# shift_reg.net
KiCad netlist of a schematic drawn in EAGLE
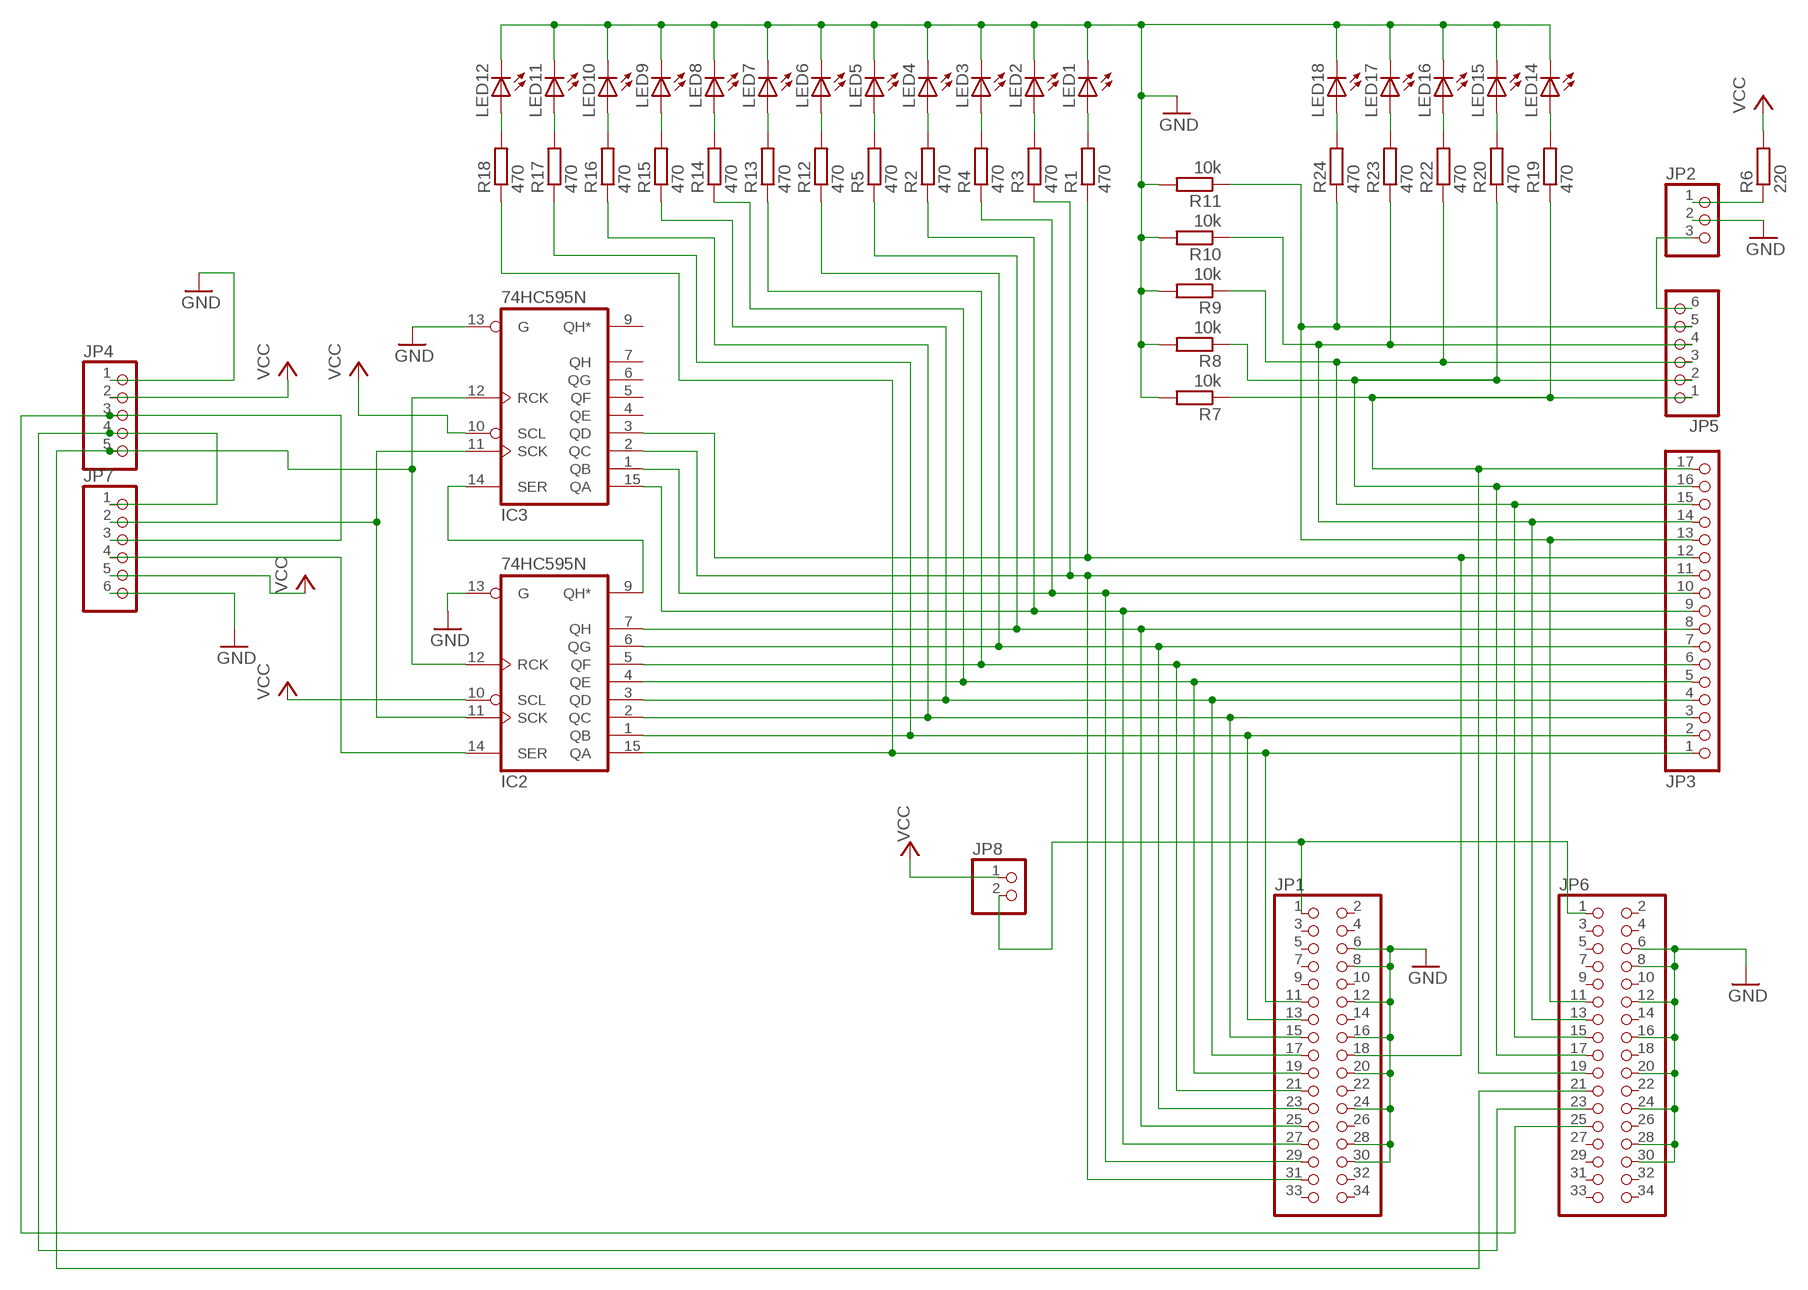
[diagram p0: schematic, sheet 1]

(export (version "E")
  (design (tool "Eeschema 10.0.6"))
  (components
    (comp (ref "IC2")
      (value "74HC595N")
      (footprint "eagle-import:DIL16")
      (libsource (lib "eagle-import") (part "74595NHC"))
    )
    (comp (ref "IC3")
      (value "74HC595N")
      (footprint "eagle-import:DIL16")
      (libsource (lib "eagle-import") (part "74595NHC"))
    )
    (comp (ref "JP1")
      (value "PINHD-2X17")
      (footprint "eagle-import:2X17")
      (libsource (lib "eagle-import") (part "PINHD-2X17"))
    )
    (comp (ref "JP2")
      (value "PINHD-1X3")
      (footprint "eagle-import:1X03")
      (libsource (lib "eagle-import") (part "PINHD-1X3"))
    )
    (comp (ref "JP3")
      (value "PINHD-1X17")
      (footprint "eagle-import:1X17")
      (libsource (lib "eagle-import") (part "PINHD-1X17"))
    )
    (comp (ref "JP4")
      (value "PINHD-1X5")
      (footprint "eagle-import:1X05")
      (libsource (lib "eagle-import") (part "PINHD-1X5"))
    )
    (comp (ref "JP5")
      (value "PINHD-1X6")
      (footprint "eagle-import:1X06")
      (libsource (lib "eagle-import") (part "PINHD-1X6"))
    )
    (comp (ref "JP6")
      (value "PINHD-2X17")
      (footprint "eagle-import:2X17")
      (libsource (lib "eagle-import") (part "PINHD-2X17"))
    )
    (comp (ref "JP7")
      (value "PINHD-1X6")
      (footprint "eagle-import:1X06")
      (libsource (lib "eagle-import") (part "PINHD-1X6"))
    )
    (comp (ref "JP8")
      (value "PINHD-1X2")
      (footprint "eagle-import:1X02")
      (libsource (lib "eagle-import") (part "PINHD-1X2"))
    )
    (comp (ref "LED1")
      (value "LED3MM")
      (footprint "eagle-import:LED3MM")
      (libsource (lib "eagle-import") (part "LED3MM"))
    )
    (comp (ref "LED2")
      (value "LED3MM")
      (footprint "eagle-import:LED3MM")
      (libsource (lib "eagle-import") (part "LED3MM"))
    )
    (comp (ref "LED3")
      (value "LED3MM")
      (footprint "eagle-import:LED3MM")
      (libsource (lib "eagle-import") (part "LED3MM"))
    )
    (comp (ref "LED4")
      (value "LED3MM")
      (footprint "eagle-import:LED3MM")
      (libsource (lib "eagle-import") (part "LED3MM"))
    )
    (comp (ref "LED5")
      (value "LED3MM")
      (footprint "eagle-import:LED3MM")
      (libsource (lib "eagle-import") (part "LED3MM"))
    )
    (comp (ref "LED6")
      (value "LED3MM")
      (footprint "eagle-import:LED3MM")
      (libsource (lib "eagle-import") (part "LED3MM"))
    )
    (comp (ref "LED7")
      (value "LED3MM")
      (footprint "eagle-import:LED3MM")
      (libsource (lib "eagle-import") (part "LED3MM"))
    )
    (comp (ref "LED8")
      (value "LED3MM")
      (footprint "eagle-import:LED3MM")
      (libsource (lib "eagle-import") (part "LED3MM"))
    )
    (comp (ref "LED9")
      (value "LED3MM")
      (footprint "eagle-import:LED3MM")
      (libsource (lib "eagle-import") (part "LED3MM"))
    )
    (comp (ref "LED10")
      (value "LED3MM")
      (footprint "eagle-import:LED3MM")
      (libsource (lib "eagle-import") (part "LED3MM"))
    )
    (comp (ref "LED11")
      (value "LED3MM")
      (footprint "eagle-import:LED3MM")
      (libsource (lib "eagle-import") (part "LED3MM"))
    )
    (comp (ref "LED12")
      (value "LED3MM")
      (footprint "eagle-import:LED3MM")
      (libsource (lib "eagle-import") (part "LED3MM"))
    )
    (comp (ref "LED14")
      (value "LED3MM")
      (footprint "eagle-import:LED3MM")
      (libsource (lib "eagle-import") (part "LED3MM"))
    )
    (comp (ref "LED15")
      (value "LED3MM")
      (footprint "eagle-import:LED3MM")
      (libsource (lib "eagle-import") (part "LED3MM"))
    )
    (comp (ref "LED16")
      (value "LED3MM")
      (footprint "eagle-import:LED3MM")
      (libsource (lib "eagle-import") (part "LED3MM"))
    )
    (comp (ref "LED17")
      (value "LED3MM")
      (footprint "eagle-import:LED3MM")
      (libsource (lib "eagle-import") (part "LED3MM"))
    )
    (comp (ref "LED18")
      (value "LED3MM")
      (footprint "eagle-import:LED3MM")
      (libsource (lib "eagle-import") (part "LED3MM"))
    )
    (comp (ref "R1")
      (value "470")
      (footprint "eagle-import:0207_10")
      (libsource (lib "eagle-import") (part "R-EU_0207/10"))
    )
    (comp (ref "R2")
      (value "470")
      (footprint "eagle-import:0207_10")
      (libsource (lib "eagle-import") (part "R-EU_0207/10"))
    )
    (comp (ref "R3")
      (value "470")
      (footprint "eagle-import:0207_10")
      (libsource (lib "eagle-import") (part "R-EU_0207/10"))
    )
    (comp (ref "R4")
      (value "470")
      (footprint "eagle-import:0207_10")
      (libsource (lib "eagle-import") (part "R-EU_0207/10"))
    )
    (comp (ref "R5")
      (value "470")
      (footprint "eagle-import:0207_10")
      (libsource (lib "eagle-import") (part "R-EU_0207/10"))
    )
    (comp (ref "R6")
      (value "220")
      (footprint "eagle-import:0207_10")
      (libsource (lib "eagle-import") (part "R-EU_0207/10"))
    )
    (comp (ref "R7")
      (value "10k")
      (footprint "eagle-import:0207_10")
      (libsource (lib "eagle-import") (part "R-EU_0207/10"))
    )
    (comp (ref "R8")
      (value "10k")
      (footprint "eagle-import:0207_10")
      (libsource (lib "eagle-import") (part "R-EU_0207/10"))
    )
    (comp (ref "R9")
      (value "10k")
      (footprint "eagle-import:0207_10")
      (libsource (lib "eagle-import") (part "R-EU_0207/10"))
    )
    (comp (ref "R10")
      (value "10k")
      (footprint "eagle-import:0207_10")
      (libsource (lib "eagle-import") (part "R-EU_0207/10"))
    )
    (comp (ref "R11")
      (value "10k")
      (footprint "eagle-import:0207_10")
      (libsource (lib "eagle-import") (part "R-EU_0207/10"))
    )
    (comp (ref "R12")
      (value "470")
      (footprint "eagle-import:0207_10")
      (libsource (lib "eagle-import") (part "R-EU_0207/10"))
    )
    (comp (ref "R13")
      (value "470")
      (footprint "eagle-import:0207_10")
      (libsource (lib "eagle-import") (part "R-EU_0207/10"))
    )
    (comp (ref "R14")
      (value "470")
      (footprint "eagle-import:0207_10")
      (libsource (lib "eagle-import") (part "R-EU_0207/10"))
    )
    (comp (ref "R15")
      (value "470")
      (footprint "eagle-import:0207_10")
      (libsource (lib "eagle-import") (part "R-EU_0207/10"))
    )
    (comp (ref "R16")
      (value "470")
      (footprint "eagle-import:0207_10")
      (libsource (lib "eagle-import") (part "R-EU_0207/10"))
    )
    (comp (ref "R17")
      (value "470")
      (footprint "eagle-import:0207_10")
      (libsource (lib "eagle-import") (part "R-EU_0207/10"))
    )
    (comp (ref "R18")
      (value "470")
      (footprint "eagle-import:0207_10")
      (libsource (lib "eagle-import") (part "R-EU_0207/10"))
    )
    (comp (ref "R19")
      (value "470")
      (footprint "eagle-import:0207_10")
      (libsource (lib "eagle-import") (part "R-EU_0207/10"))
    )
    (comp (ref "R20")
      (value "470")
      (footprint "eagle-import:0207_10")
      (libsource (lib "eagle-import") (part "R-EU_0207/10"))
    )
    (comp (ref "R22")
      (value "470")
      (footprint "eagle-import:0207_10")
      (libsource (lib "eagle-import") (part "R-EU_0207/10"))
    )
    (comp (ref "R23")
      (value "470")
      (footprint "eagle-import:0207_10")
      (libsource (lib "eagle-import") (part "R-EU_0207/10"))
    )
    (comp (ref "R24")
      (value "470")
      (footprint "eagle-import:0207_10")
      (libsource (lib "eagle-import") (part "R-EU_0207/10"))
    )
  )
  (nets
    (net (code "1") (name "GND") (class "Default")
      (node (ref "IC2") (pin "13") (pinfunction "G_13") (pintype "input"))
      (node (ref "IC3") (pin "13") (pinfunction "G_13") (pintype "input"))
      (node (ref "JP1") (pin "12") (pinfunction "12_12") (pintype "passive"))
      (node (ref "JP1") (pin "16") (pinfunction "16_16") (pintype "passive"))
      (node (ref "JP1") (pin "20") (pinfunction "20_20") (pintype "passive"))
      (node (ref "JP1") (pin "24") (pinfunction "24_24") (pintype "passive"))
      (node (ref "JP1") (pin "28") (pinfunction "28_28") (pintype "passive"))
      (node (ref "JP1") (pin "30") (pinfunction "30_30") (pintype "passive"))
      (node (ref "JP1") (pin "6") (pinfunction "6_6") (pintype "passive"))
      (node (ref "JP1") (pin "8") (pinfunction "8_8") (pintype "passive"))
      (node (ref "JP2") (pin "2") (pinfunction "2_2") (pintype "passive"))
      (node (ref "JP4") (pin "1") (pinfunction "1_1") (pintype "passive"))
      (node (ref "JP6") (pin "12") (pinfunction "12_12") (pintype "passive"))
      (node (ref "JP6") (pin "16") (pinfunction "16_16") (pintype "passive"))
      (node (ref "JP6") (pin "20") (pinfunction "20_20") (pintype "passive"))
      (node (ref "JP6") (pin "24") (pinfunction "24_24") (pintype "passive"))
      (node (ref "JP6") (pin "28") (pinfunction "28_28") (pintype "passive"))
      (node (ref "JP6") (pin "30") (pinfunction "30_30") (pintype "passive"))
      (node (ref "JP6") (pin "6") (pinfunction "6_6") (pintype "passive"))
      (node (ref "JP6") (pin "8") (pinfunction "8_8") (pintype "passive"))
      (node (ref "JP7") (pin "6") (pinfunction "6_6") (pintype "passive"))
      (node (ref "LED1") (pin "K") (pinfunction "C_K") (pintype "passive"))
      (node (ref "LED10") (pin "K") (pinfunction "C_K") (pintype "passive"))
      (node (ref "LED11") (pin "K") (pinfunction "C_K") (pintype "passive"))
      (node (ref "LED12") (pin "K") (pinfunction "C_K") (pintype "passive"))
      (node (ref "LED14") (pin "K") (pinfunction "C_K") (pintype "passive"))
      (node (ref "LED15") (pin "K") (pinfunction "C_K") (pintype "passive"))
      (node (ref "LED16") (pin "K") (pinfunction "C_K") (pintype "passive"))
      (node (ref "LED17") (pin "K") (pinfunction "C_K") (pintype "passive"))
      (node (ref "LED18") (pin "K") (pinfunction "C_K") (pintype "passive"))
      (node (ref "LED2") (pin "K") (pinfunction "C_K") (pintype "passive"))
      (node (ref "LED3") (pin "K") (pinfunction "C_K") (pintype "passive"))
      (node (ref "LED4") (pin "K") (pinfunction "C_K") (pintype "passive"))
      (node (ref "LED5") (pin "K") (pinfunction "C_K") (pintype "passive"))
      (node (ref "LED6") (pin "K") (pinfunction "C_K") (pintype "passive"))
      (node (ref "LED7") (pin "K") (pinfunction "C_K") (pintype "passive"))
      (node (ref "LED8") (pin "K") (pinfunction "C_K") (pintype "passive"))
      (node (ref "LED9") (pin "K") (pinfunction "C_K") (pintype "passive"))
      (node (ref "R10") (pin "2") (pinfunction "2_2") (pintype "passive"))
      (node (ref "R11") (pin "2") (pinfunction "2_2") (pintype "passive"))
      (node (ref "R7") (pin "2") (pinfunction "2_2") (pintype "passive"))
      (node (ref "R8") (pin "2") (pinfunction "2_2") (pintype "passive"))
      (node (ref "R9") (pin "2") (pinfunction "2_2") (pintype "passive"))
    )
    (net (code "2") (name "Net-(IC2A-QA)") (class "Default")
      (node (ref "IC2") (pin "15") (pinfunction "QA_15") (pintype "tri_state"))
      (node (ref "JP1") (pin "11") (pinfunction "11_11") (pintype "passive"))
      (node (ref "JP3") (pin "1") (pinfunction "1_1") (pintype "passive"))
      (node (ref "R18") (pin "1") (pinfunction "1_1") (pintype "passive"))
    )
    (net (code "3") (name "Net-(IC2A-QB)") (class "Default")
      (node (ref "IC2") (pin "1") (pinfunction "QB_1") (pintype "tri_state"))
      (node (ref "JP1") (pin "13") (pinfunction "13_13") (pintype "passive"))
      (node (ref "JP3") (pin "2") (pinfunction "2_2") (pintype "passive"))
      (node (ref "R17") (pin "1") (pinfunction "1_1") (pintype "passive"))
    )
    (net (code "4") (name "Net-(IC2A-QC)") (class "Default")
      (node (ref "IC2") (pin "2") (pinfunction "QC_2") (pintype "tri_state"))
      (node (ref "JP1") (pin "15") (pinfunction "15_15") (pintype "passive"))
      (node (ref "JP3") (pin "3") (pinfunction "3_3") (pintype "passive"))
      (node (ref "R16") (pin "1") (pinfunction "1_1") (pintype "passive"))
    )
    (net (code "5") (name "Net-(IC2A-QD)") (class "Default")
      (node (ref "IC2") (pin "3") (pinfunction "QD_3") (pintype "tri_state"))
      (node (ref "JP1") (pin "17") (pinfunction "17_17") (pintype "passive"))
      (node (ref "JP3") (pin "4") (pinfunction "4_4") (pintype "passive"))
      (node (ref "R15") (pin "1") (pinfunction "1_1") (pintype "passive"))
    )
    (net (code "6") (name "Net-(IC2A-QE)") (class "Default")
      (node (ref "IC2") (pin "4") (pinfunction "QE_4") (pintype "tri_state"))
      (node (ref "JP1") (pin "19") (pinfunction "19_19") (pintype "passive"))
      (node (ref "JP3") (pin "5") (pinfunction "5_5") (pintype "passive"))
      (node (ref "R14") (pin "1") (pinfunction "1_1") (pintype "passive"))
    )
    (net (code "7") (name "Net-(IC2A-QF)") (class "Default")
      (node (ref "IC2") (pin "5") (pinfunction "QF_5") (pintype "tri_state"))
      (node (ref "JP1") (pin "21") (pinfunction "21_21") (pintype "passive"))
      (node (ref "JP3") (pin "6") (pinfunction "6_6") (pintype "passive"))
      (node (ref "R13") (pin "1") (pinfunction "1_1") (pintype "passive"))
    )
    (net (code "8") (name "Net-(IC2A-QG)") (class "Default")
      (node (ref "IC2") (pin "6") (pinfunction "QG_6") (pintype "tri_state"))
      (node (ref "JP1") (pin "23") (pinfunction "23_23") (pintype "passive"))
      (node (ref "JP3") (pin "7") (pinfunction "7_7") (pintype "passive"))
      (node (ref "R12") (pin "1") (pinfunction "1_1") (pintype "passive"))
    )
    (net (code "9") (name "Net-(IC2A-QH)") (class "Default")
      (node (ref "IC2") (pin "7") (pinfunction "QH_7") (pintype "tri_state"))
      (node (ref "JP1") (pin "25") (pinfunction "25_25") (pintype "passive"))
      (node (ref "JP3") (pin "8") (pinfunction "8_8") (pintype "passive"))
      (node (ref "R5") (pin "1") (pinfunction "1_1") (pintype "passive"))
    )
    (net (code "10") (name "Net-(IC2A-QH*)") (class "Default")
      (node (ref "IC2") (pin "9") (pinfunction "QH*_9") (pintype "tri_state"))
      (node (ref "IC3") (pin "14") (pinfunction "SER_14") (pintype "input"))
    )
    (net (code "11") (name "Net-(IC2A-RCK)") (class "Default")
      (node (ref "IC2") (pin "12") (pinfunction "RCK_12") (pintype "input"))
      (node (ref "IC3") (pin "12") (pinfunction "RCK_12") (pintype "input"))
      (node (ref "JP4") (pin "5") (pinfunction "5_5") (pintype "passive"))
      (node (ref "JP6") (pin "21") (pinfunction "21_21") (pintype "passive"))
    )
    (net (code "12") (name "Net-(IC2A-SCK)") (class "Default")
      (node (ref "IC2") (pin "11") (pinfunction "SCK_11") (pintype "input"))
      (node (ref "IC3") (pin "11") (pinfunction "SCK_11") (pintype "input"))
      (node (ref "JP7") (pin "2") (pinfunction "2_2") (pintype "passive"))
    )
    (net (code "13") (name "Net-(IC2A-SER)") (class "Default")
      (node (ref "IC2") (pin "14") (pinfunction "SER_14") (pintype "input"))
      (node (ref "JP7") (pin "4") (pinfunction "4_4") (pintype "passive"))
    )
    (net (code "14") (name "Net-(IC3A-QA)") (class "Default")
      (node (ref "IC3") (pin "15") (pinfunction "QA_15") (pintype "tri_state"))
      (node (ref "JP1") (pin "27") (pinfunction "27_27") (pintype "passive"))
      (node (ref "JP3") (pin "9") (pinfunction "9_9") (pintype "passive"))
      (node (ref "R2") (pin "1") (pinfunction "1_1") (pintype "passive"))
    )
    (net (code "15") (name "Net-(IC3A-QB)") (class "Default")
      (node (ref "IC3") (pin "1") (pinfunction "QB_1") (pintype "tri_state"))
      (node (ref "JP1") (pin "29") (pinfunction "29_29") (pintype "passive"))
      (node (ref "JP3") (pin "10") (pinfunction "10_10") (pintype "passive"))
      (node (ref "R4") (pin "1") (pinfunction "1_1") (pintype "passive"))
    )
    (net (code "16") (name "Net-(IC3A-QC)") (class "Default")
      (node (ref "IC3") (pin "2") (pinfunction "QC_2") (pintype "tri_state"))
      (node (ref "JP1") (pin "31") (pinfunction "31_31") (pintype "passive"))
      (node (ref "JP3") (pin "11") (pinfunction "11_11") (pintype "passive"))
      (node (ref "R3") (pin "1") (pinfunction "1_1") (pintype "passive"))
    )
    (net (code "17") (name "Net-(IC3A-QD)") (class "Default")
      (node (ref "IC3") (pin "3") (pinfunction "QD_3") (pintype "tri_state"))
      (node (ref "JP1") (pin "18") (pinfunction "18_18") (pintype "passive"))
      (node (ref "JP3") (pin "12") (pinfunction "12_12") (pintype "passive"))
      (node (ref "R1") (pin "1") (pinfunction "1_1") (pintype "passive"))
    )
    (net (code "18") (name "Net-(JP1-Pad1)") (class "Default")
      (node (ref "JP1") (pin "1") (pinfunction "1_1") (pintype "passive"))
      (node (ref "JP6") (pin "1") (pinfunction "1_1") (pintype "passive"))
      (node (ref "JP8") (pin "2") (pinfunction "2_2") (pintype "passive"))
    )
    (net (code "19") (name "Net-(JP2-Pad1)") (class "Default")
      (node (ref "JP2") (pin "1") (pinfunction "1_1") (pintype "passive"))
      (node (ref "R6") (pin "1") (pinfunction "1_1") (pintype "passive"))
    )
    (net (code "20") (name "Net-(JP2-Pad3)") (class "Default")
      (node (ref "JP2") (pin "3") (pinfunction "3_3") (pintype "passive"))
      (node (ref "JP5") (pin "6") (pinfunction "6_6") (pintype "passive"))
    )
    (net (code "21") (name "Net-(JP3-Pad13)") (class "Default")
      (node (ref "JP3") (pin "13") (pinfunction "13_13") (pintype "passive"))
      (node (ref "JP5") (pin "5") (pinfunction "5_5") (pintype "passive"))
      (node (ref "JP6") (pin "11") (pinfunction "11_11") (pintype "passive"))
      (node (ref "R11") (pin "1") (pinfunction "1_1") (pintype "passive"))
      (node (ref "R24") (pin "1") (pinfunction "1_1") (pintype "passive"))
    )
    (net (code "22") (name "Net-(JP3-Pad14)") (class "Default")
      (node (ref "JP3") (pin "14") (pinfunction "14_14") (pintype "passive"))
      (node (ref "JP5") (pin "4") (pinfunction "4_4") (pintype "passive"))
      (node (ref "JP6") (pin "13") (pinfunction "13_13") (pintype "passive"))
      (node (ref "R10") (pin "1") (pinfunction "1_1") (pintype "passive"))
      (node (ref "R23") (pin "1") (pinfunction "1_1") (pintype "passive"))
    )
    (net (code "23") (name "Net-(JP3-Pad15)") (class "Default")
      (node (ref "JP3") (pin "15") (pinfunction "15_15") (pintype "passive"))
      (node (ref "JP5") (pin "3") (pinfunction "3_3") (pintype "passive"))
      (node (ref "JP6") (pin "15") (pinfunction "15_15") (pintype "passive"))
      (node (ref "R22") (pin "1") (pinfunction "1_1") (pintype "passive"))
      (node (ref "R9") (pin "1") (pinfunction "1_1") (pintype "passive"))
    )
    (net (code "24") (name "Net-(JP3-Pad16)") (class "Default")
      (node (ref "JP3") (pin "16") (pinfunction "16_16") (pintype "passive"))
      (node (ref "JP5") (pin "2") (pinfunction "2_2") (pintype "passive"))
      (node (ref "JP6") (pin "17") (pinfunction "17_17") (pintype "passive"))
      (node (ref "R20") (pin "1") (pinfunction "1_1") (pintype "passive"))
      (node (ref "R8") (pin "1") (pinfunction "1_1") (pintype "passive"))
    )
    (net (code "25") (name "Net-(JP3-Pad17)") (class "Default")
      (node (ref "JP3") (pin "17") (pinfunction "17_17") (pintype "passive"))
      (node (ref "JP5") (pin "1") (pinfunction "1_1") (pintype "passive"))
      (node (ref "JP6") (pin "19") (pinfunction "19_19") (pintype "passive"))
      (node (ref "R19") (pin "1") (pinfunction "1_1") (pintype "passive"))
      (node (ref "R7") (pin "1") (pinfunction "1_1") (pintype "passive"))
    )
    (net (code "26") (name "Net-(JP4-Pad3)") (class "Default")
      (node (ref "JP4") (pin "3") (pinfunction "3_3") (pintype "passive"))
      (node (ref "JP6") (pin "25") (pinfunction "25_25") (pintype "passive"))
      (node (ref "JP7") (pin "3") (pinfunction "3_3") (pintype "passive"))
    )
    (net (code "27") (name "Net-(JP4-Pad4)") (class "Default")
      (node (ref "JP4") (pin "4") (pinfunction "4_4") (pintype "passive"))
      (node (ref "JP6") (pin "23") (pinfunction "23_23") (pintype "passive"))
      (node (ref "JP7") (pin "1") (pinfunction "1_1") (pintype "passive"))
    )
    (net (code "28") (name "Net-(LED1-PadA)") (class "Default")
      (node (ref "LED1") (pin "A") (pinfunction "A_A") (pintype "passive"))
      (node (ref "R1") (pin "2") (pinfunction "2_2") (pintype "passive"))
    )
    (net (code "29") (name "Net-(LED2-PadA)") (class "Default")
      (node (ref "LED2") (pin "A") (pinfunction "A_A") (pintype "passive"))
      (node (ref "R3") (pin "2") (pinfunction "2_2") (pintype "passive"))
    )
    (net (code "30") (name "Net-(LED3-PadA)") (class "Default")
      (node (ref "LED3") (pin "A") (pinfunction "A_A") (pintype "passive"))
      (node (ref "R4") (pin "2") (pinfunction "2_2") (pintype "passive"))
    )
    (net (code "31") (name "Net-(LED4-PadA)") (class "Default")
      (node (ref "LED4") (pin "A") (pinfunction "A_A") (pintype "passive"))
      (node (ref "R2") (pin "2") (pinfunction "2_2") (pintype "passive"))
    )
    (net (code "32") (name "Net-(LED5-PadA)") (class "Default")
      (node (ref "LED5") (pin "A") (pinfunction "A_A") (pintype "passive"))
      (node (ref "R5") (pin "2") (pinfunction "2_2") (pintype "passive"))
    )
    (net (code "33") (name "Net-(LED6-PadA)") (class "Default")
      (node (ref "LED6") (pin "A") (pinfunction "A_A") (pintype "passive"))
      (node (ref "R12") (pin "2") (pinfunction "2_2") (pintype "passive"))
    )
    (net (code "34") (name "Net-(LED7-PadA)") (class "Default")
      (node (ref "LED7") (pin "A") (pinfunction "A_A") (pintype "passive"))
      (node (ref "R13") (pin "2") (pinfunction "2_2") (pintype "passive"))
    )
    (net (code "35") (name "Net-(LED8-PadA)") (class "Default")
      (node (ref "LED8") (pin "A") (pinfunction "A_A") (pintype "passive"))
      (node (ref "R14") (pin "2") (pinfunction "2_2") (pintype "passive"))
    )
    (net (code "36") (name "Net-(LED9-PadA)") (class "Default")
      (node (ref "LED9") (pin "A") (pinfunction "A_A") (pintype "passive"))
      (node (ref "R15") (pin "2") (pinfunction "2_2") (pintype "passive"))
    )
    (net (code "37") (name "Net-(LED10-PadA)") (class "Default")
      (node (ref "LED10") (pin "A") (pinfunction "A_A") (pintype "passive"))
      (node (ref "R16") (pin "2") (pinfunction "2_2") (pintype "passive"))
    )
    (net (code "38") (name "Net-(LED11-PadA)") (class "Default")
      (node (ref "LED11") (pin "A") (pinfunction "A_A") (pintype "passive"))
      (node (ref "R17") (pin "2") (pinfunction "2_2") (pintype "passive"))
    )
    (net (code "39") (name "Net-(LED12-PadA)") (class "Default")
      (node (ref "LED12") (pin "A") (pinfunction "A_A") (pintype "passive"))
      (node (ref "R18") (pin "2") (pinfunction "2_2") (pintype "passive"))
    )
    (net (code "40") (name "Net-(LED14-PadA)") (class "Default")
      (node (ref "LED14") (pin "A") (pinfunction "A_A") (pintype "passive"))
      (node (ref "R19") (pin "2") (pinfunction "2_2") (pintype "passive"))
    )
    (net (code "41") (name "Net-(LED15-PadA)") (class "Default")
      (node (ref "LED15") (pin "A") (pinfunction "A_A") (pintype "passive"))
      (node (ref "R20") (pin "2") (pinfunction "2_2") (pintype "passive"))
    )
    (net (code "42") (name "Net-(LED16-PadA)") (class "Default")
      (node (ref "LED16") (pin "A") (pinfunction "A_A") (pintype "passive"))
      (node (ref "R22") (pin "2") (pinfunction "2_2") (pintype "passive"))
    )
    (net (code "43") (name "Net-(LED17-PadA)") (class "Default")
      (node (ref "LED17") (pin "A") (pinfunction "A_A") (pintype "passive"))
      (node (ref "R23") (pin "2") (pinfunction "2_2") (pintype "passive"))
    )
    (net (code "44") (name "Net-(LED18-PadA)") (class "Default")
      (node (ref "LED18") (pin "A") (pinfunction "A_A") (pintype "passive"))
      (node (ref "R24") (pin "2") (pinfunction "2_2") (pintype "passive"))
    )
    (net (code "45") (name "VCC") (class "Default")
      (node (ref "IC2") (pin "10") (pinfunction "SCL_10") (pintype "input"))
      (node (ref "IC3") (pin "10") (pinfunction "SCL_10") (pintype "input"))
      (node (ref "JP4") (pin "2") (pinfunction "2_2") (pintype "passive"))
      (node (ref "JP7") (pin "5") (pinfunction "5_5") (pintype "passive"))
      (node (ref "JP8") (pin "1") (pinfunction "1_1") (pintype "passive"))
      (node (ref "R6") (pin "2") (pinfunction "2_2") (pintype "passive"))
    )
    (net (code "46") (name "unconnected-(IC3A-QE-Pad4)") (class "Default")
      (node (ref "IC3") (pin "4") (pinfunction "QE_4") (pintype "tri_state"))
    )
    (net (code "47") (name "unconnected-(IC3A-QF-Pad5)") (class "Default")
      (node (ref "IC3") (pin "5") (pinfunction "QF_5") (pintype "tri_state"))
    )
    (net (code "48") (name "unconnected-(IC3A-QG-Pad6)") (class "Default")
      (node (ref "IC3") (pin "6") (pinfunction "QG_6") (pintype "tri_state"))
    )
    (net (code "49") (name "unconnected-(IC3A-QH*-Pad9)") (class "Default")
      (node (ref "IC3") (pin "9") (pinfunction "QH*_9") (pintype "tri_state"))
    )
    (net (code "50") (name "unconnected-(IC3A-QH-Pad7)") (class "Default")
      (node (ref "IC3") (pin "7") (pinfunction "QH_7") (pintype "tri_state"))
    )
    (net (code "51") (name "unconnected-(JP1-Pad2)") (class "Default")
      (node (ref "JP1") (pin "2") (pinfunction "2_2") (pintype "passive"))
    )
    (net (code "52") (name "unconnected-(JP1-Pad3)") (class "Default")
      (node (ref "JP1") (pin "3") (pinfunction "3_3") (pintype "passive"))
    )
    (net (code "53") (name "unconnected-(JP1-Pad4)") (class "Default")
      (node (ref "JP1") (pin "4") (pinfunction "4_4") (pintype "passive"))
    )
    (net (code "54") (name "unconnected-(JP1-Pad5)") (class "Default")
      (node (ref "JP1") (pin "5") (pinfunction "5_5") (pintype "passive"))
    )
    (net (code "55") (name "unconnected-(JP1-Pad7)") (class "Default")
      (node (ref "JP1") (pin "7") (pinfunction "7_7") (pintype "passive"))
    )
    (net (code "56") (name "unconnected-(JP1-Pad9)") (class "Default")
      (node (ref "JP1") (pin "9") (pinfunction "9_9") (pintype "passive"))
    )
    (net (code "57") (name "unconnected-(JP1-Pad10)") (class "Default")
      (node (ref "JP1") (pin "10") (pinfunction "10_10") (pintype "passive"))
    )
    (net (code "58") (name "unconnected-(JP1-Pad14)") (class "Default")
      (node (ref "JP1") (pin "14") (pinfunction "14_14") (pintype "passive"))
    )
    (net (code "59") (name "unconnected-(JP1-Pad22)") (class "Default")
      (node (ref "JP1") (pin "22") (pinfunction "22_22") (pintype "passive"))
    )
    (net (code "60") (name "unconnected-(JP1-Pad26)") (class "Default")
      (node (ref "JP1") (pin "26") (pinfunction "26_26") (pintype "passive"))
    )
    (net (code "61") (name "unconnected-(JP1-Pad32)") (class "Default")
      (node (ref "JP1") (pin "32") (pinfunction "32_32") (pintype "passive"))
    )
    (net (code "62") (name "unconnected-(JP1-Pad33)") (class "Default")
      (node (ref "JP1") (pin "33") (pinfunction "33_33") (pintype "passive"))
    )
    (net (code "63") (name "unconnected-(JP1-Pad34)") (class "Default")
      (node (ref "JP1") (pin "34") (pinfunction "34_34") (pintype "passive"))
    )
    (net (code "64") (name "unconnected-(JP6-Pad2)") (class "Default")
      (node (ref "JP6") (pin "2") (pinfunction "2_2") (pintype "passive"))
    )
    (net (code "65") (name "unconnected-(JP6-Pad3)") (class "Default")
      (node (ref "JP6") (pin "3") (pinfunction "3_3") (pintype "passive"))
    )
    (net (code "66") (name "unconnected-(JP6-Pad4)") (class "Default")
      (node (ref "JP6") (pin "4") (pinfunction "4_4") (pintype "passive"))
    )
    (net (code "67") (name "unconnected-(JP6-Pad5)") (class "Default")
      (node (ref "JP6") (pin "5") (pinfunction "5_5") (pintype "passive"))
    )
    (net (code "68") (name "unconnected-(JP6-Pad7)") (class "Default")
      (node (ref "JP6") (pin "7") (pinfunction "7_7") (pintype "passive"))
    )
    (net (code "69") (name "unconnected-(JP6-Pad9)") (class "Default")
      (node (ref "JP6") (pin "9") (pinfunction "9_9") (pintype "passive"))
    )
    (net (code "70") (name "unconnected-(JP6-Pad10)") (class "Default")
      (node (ref "JP6") (pin "10") (pinfunction "10_10") (pintype "passive"))
    )
    (net (code "71") (name "unconnected-(JP6-Pad14)") (class "Default")
      (node (ref "JP6") (pin "14") (pinfunction "14_14") (pintype "passive"))
    )
    (net (code "72") (name "unconnected-(JP6-Pad18)") (class "Default")
      (node (ref "JP6") (pin "18") (pinfunction "18_18") (pintype "passive"))
    )
    (net (code "73") (name "unconnected-(JP6-Pad22)") (class "Default")
      (node (ref "JP6") (pin "22") (pinfunction "22_22") (pintype "passive"))
    )
    (net (code "74") (name "unconnected-(JP6-Pad26)") (class "Default")
      (node (ref "JP6") (pin "26") (pinfunction "26_26") (pintype "passive"))
    )
    (net (code "75") (name "unconnected-(JP6-Pad27)") (class "Default")
      (node (ref "JP6") (pin "27") (pinfunction "27_27") (pintype "passive"))
    )
    (net (code "76") (name "unconnected-(JP6-Pad29)") (class "Default")
      (node (ref "JP6") (pin "29") (pinfunction "29_29") (pintype "passive"))
    )
    (net (code "77") (name "unconnected-(JP6-Pad31)") (class "Default")
      (node (ref "JP6") (pin "31") (pinfunction "31_31") (pintype "passive"))
    )
    (net (code "78") (name "unconnected-(JP6-Pad32)") (class "Default")
      (node (ref "JP6") (pin "32") (pinfunction "32_32") (pintype "passive"))
    )
    (net (code "79") (name "unconnected-(JP6-Pad33)") (class "Default")
      (node (ref "JP6") (pin "33") (pinfunction "33_33") (pintype "passive"))
    )
    (net (code "80") (name "unconnected-(JP6-Pad34)") (class "Default")
      (node (ref "JP6") (pin "34") (pinfunction "34_34") (pintype "passive"))
    )
  )
)
